# BYOB-BoosterPack-Template.net
KiCad netlist of a schematic drawn in EAGLE
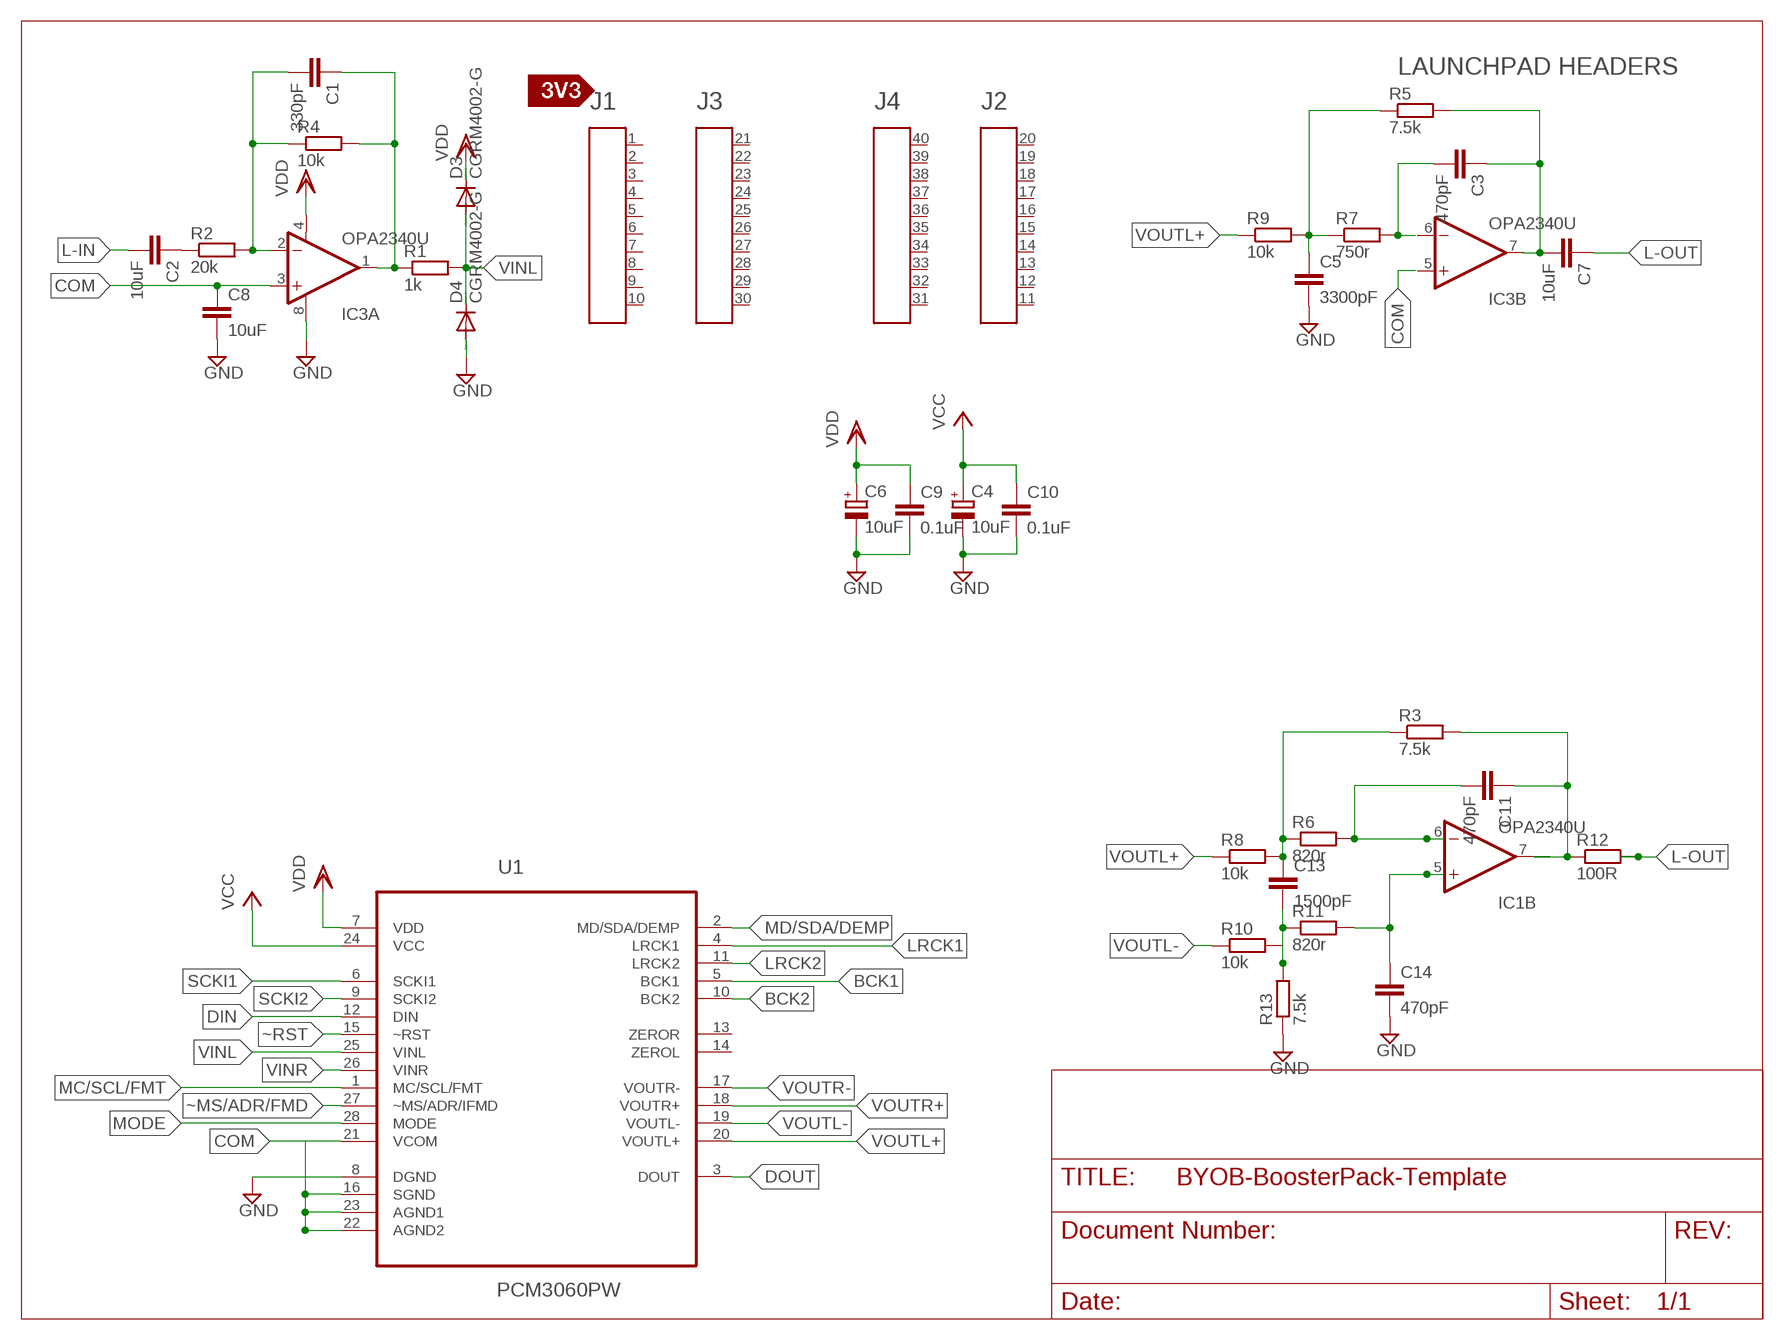
[diagram p0: schematic, sheet 1]

(export (version "E")
  (design (tool "Eeschema 10.0.6"))
  (components
    (comp (ref "A1")
      (value "HEADER4X10-BOOSTERPACK")
      (footprint "eagle-import:4X10-BOOSTERPACK")
      (libsource (lib "eagle-import") (part "HEADER4X10-BOOSTERPACK"))
    )
    (comp (ref "C1")
      (value "330pF")
      (footprint "eagle-import:C1608")
      (libsource (lib "eagle-import") (part "C-EUC1608"))
    )
    (comp (ref "C2")
      (value "10uF")
      (footprint "eagle-import:C1608")
      (libsource (lib "eagle-import") (part "C-EUC1608"))
    )
    (comp (ref "C3")
      (value "470pF")
      (footprint "eagle-import:C1608")
      (libsource (lib "eagle-import") (part "C-EUC1608"))
    )
    (comp (ref "C4")
      (value "10uF")
      (footprint "eagle-import:150CLZ-1010")
      (libsource (lib "eagle-import") (part "CPOL-EU150CLZ-1010"))
    )
    (comp (ref "C5")
      (value "3300pF")
      (footprint "eagle-import:C1608")
      (libsource (lib "eagle-import") (part "C-EUC1608"))
    )
    (comp (ref "C6")
      (value "10uF")
      (footprint "eagle-import:150CLZ-1010")
      (libsource (lib "eagle-import") (part "CPOL-EU150CLZ-1010"))
    )
    (comp (ref "C7")
      (value "10uF")
      (footprint "eagle-import:C1608")
      (libsource (lib "eagle-import") (part "C-EUC1608"))
    )
    (comp (ref "C8")
      (value "10uF")
      (footprint "eagle-import:C1608")
      (libsource (lib "eagle-import") (part "C-EUC1608"))
    )
    (comp (ref "C9")
      (value "0.1uF")
      (footprint "eagle-import:C1608")
      (libsource (lib "eagle-import") (part "C-EUC1608"))
    )
    (comp (ref "C10")
      (value "0.1uF")
      (footprint "eagle-import:C1608")
      (libsource (lib "eagle-import") (part "C-EUC1608"))
    )
    (comp (ref "C11")
      (value "470pF")
      (footprint "eagle-import:C1608")
      (libsource (lib "eagle-import") (part "C-EUC1608"))
    )
    (comp (ref "C13")
      (value "1500pF")
      (footprint "eagle-import:C1608")
      (libsource (lib "eagle-import") (part "C-EUC1608"))
    )
    (comp (ref "C14")
      (value "470pF")
      (footprint "eagle-import:C1608")
      (libsource (lib "eagle-import") (part "C-EUC1608"))
    )
    (comp (ref "D3")
      (value "CGRM4002-G")
      (footprint "eagle-import:SOD-123_MINI-SMA")
      (libsource (lib "eagle-import") (part "CGRM400-G2"))
    )
    (comp (ref "D4")
      (value "CGRM4002-G")
      (footprint "eagle-import:SOD-123_MINI-SMA")
      (libsource (lib "eagle-import") (part "CGRM400-G2"))
    )
    (comp (ref "IC1")
      (value "OPA2340U")
      (footprint "eagle-import:SO08")
      (fields (field (name "MF") "TEXAS INSTRUMENTS") (field (name "MPN") "OPA2340UA"))
      (libsource (lib "eagle-import") (part "OPA2340U"))
    )
    (comp (ref "IC3")
      (value "OPA2340U")
      (footprint "eagle-import:SO08")
      (fields (field (name "MF") "TEXAS INSTRUMENTS") (field (name "MPN") "OPA2340UA"))
      (libsource (lib "eagle-import") (part "OPA2340U"))
    )
    (comp (ref "R1")
      (value "1k")
      (footprint "eagle-import:R1206")
      (libsource (lib "eagle-import") (part "R-EU_R1206"))
    )
    (comp (ref "R2")
      (value "20k")
      (footprint "eagle-import:R1206")
      (libsource (lib "eagle-import") (part "R-EU_R1206"))
    )
    (comp (ref "R3")
      (value "7.5k")
      (footprint "eagle-import:R1206")
      (libsource (lib "eagle-import") (part "R-EU_R1206"))
    )
    (comp (ref "R4")
      (value "10k")
      (footprint "eagle-import:R1206")
      (libsource (lib "eagle-import") (part "R-EU_R1206"))
    )
    (comp (ref "R5")
      (value "7.5k")
      (footprint "eagle-import:R1206")
      (libsource (lib "eagle-import") (part "R-EU_R1206"))
    )
    (comp (ref "R6")
      (value "820r")
      (footprint "eagle-import:R1206")
      (libsource (lib "eagle-import") (part "R-EU_R1206"))
    )
    (comp (ref "R7")
      (value "750r")
      (footprint "eagle-import:R1206")
      (libsource (lib "eagle-import") (part "R-EU_R1206"))
    )
    (comp (ref "R8")
      (value "10k")
      (footprint "eagle-import:R1206")
      (libsource (lib "eagle-import") (part "R-EU_R1206"))
    )
    (comp (ref "R9")
      (value "10k")
      (footprint "eagle-import:R1206")
      (libsource (lib "eagle-import") (part "R-EU_R1206"))
    )
    (comp (ref "R10")
      (value "10k")
      (footprint "eagle-import:R1206")
      (libsource (lib "eagle-import") (part "R-EU_R1206"))
    )
    (comp (ref "R11")
      (value "820r")
      (footprint "eagle-import:R1206")
      (libsource (lib "eagle-import") (part "R-EU_R1206"))
    )
    (comp (ref "R12")
      (value "100R")
      (footprint "eagle-import:R1206")
      (libsource (lib "eagle-import") (part "R-EU_R1206"))
    )
    (comp (ref "R13")
      (value "7.5k")
      (footprint "eagle-import:R1206")
      (libsource (lib "eagle-import") (part "R-EU_R1206"))
    )
    (comp (ref "U$3")
      (value "SILK_3V3_TAG")
      (footprint "eagle-import:SILK_3V3_TAG")
      (libsource (lib "eagle-import") (part "SILK_3V3_TAG"))
    )
    (comp (ref "U1")
      (value "PCM3060PW")
      (footprint "eagle-import:SOP65P640X120-28N")
      (libsource (lib "eagle-import") (part "PCM3060PW"))
    )
  )
  (nets
    (net (code "1") (name "/~{MS{slash}ADR{slash}FMD}") (class "Default")
      (node (ref "U1") (pin "27") (pinfunction "~{MS/ADR/IFMD}_27") (pintype "input"))
    )
    (net (code "2") (name "/~{RST}") (class "Default")
      (node (ref "U1") (pin "15") (pinfunction "~{RST}_15") (pintype "input"))
    )
    (net (code "3") (name "BCK1") (class "Default")
      (node (ref "U1") (pin "5") (pinfunction "BCK1_5") (pintype "bidirectional"))
    )
    (net (code "4") (name "BCK2") (class "Default")
      (node (ref "U1") (pin "10") (pinfunction "BCK2_10") (pintype "bidirectional"))
    )
    (net (code "5") (name "COM") (class "Default")
      (node (ref "C14") (pin "1") (pinfunction "1_1") (pintype "passive"))
      (node (ref "C8") (pin "1") (pinfunction "1_1") (pintype "passive"))
      (node (ref "IC1") (pin "5") (pinfunction "+IN_5") (pintype "input"))
      (node (ref "IC3") (pin "3") (pinfunction "+IN_3") (pintype "input"))
      (node (ref "R11") (pin "2") (pinfunction "2_2") (pintype "passive"))
      (node (ref "U1") (pin "16") (pinfunction "SGND_16") (pintype "passive"))
      (node (ref "U1") (pin "21") (pinfunction "VCOM_21") (pintype "passive"))
      (node (ref "U1") (pin "22") (pinfunction "AGND2_22") (pintype "passive"))
      (node (ref "U1") (pin "23") (pinfunction "AGND1_23") (pintype "passive"))
    )
    (net (code "6") (name "DIN") (class "Default")
      (node (ref "U1") (pin "12") (pinfunction "DIN_12") (pintype "input"))
    )
    (net (code "7") (name "DOUT") (class "Default")
      (node (ref "U1") (pin "3") (pinfunction "DOUT_3") (pintype "output"))
    )
    (net (code "8") (name "GND") (class "Default")
      (node (ref "C10") (pin "2") (pinfunction "2_2") (pintype "passive"))
      (node (ref "C14") (pin "2") (pinfunction "2_2") (pintype "passive"))
      (node (ref "C4") (pin "-") (pinfunction "-_-") (pintype "passive"))
      (node (ref "C5") (pin "2") (pinfunction "2_2") (pintype "passive"))
      (node (ref "C6") (pin "-") (pinfunction "-_-") (pintype "passive"))
      (node (ref "C8") (pin "2") (pinfunction "2_2") (pintype "passive"))
      (node (ref "C9") (pin "2") (pinfunction "2_2") (pintype "passive"))
      (node (ref "D4") (pin "A") (pinfunction "A_A") (pintype "passive"))
      (node (ref "IC3") (pin "8") (pinfunction "V+_8") (pintype "power_in"))
      (node (ref "R13") (pin "1") (pinfunction "1_1") (pintype "passive"))
      (node (ref "U1") (pin "8") (pinfunction "DGND_8") (pintype "passive"))
    )
    (net (code "9") (name "L-IN") (class "Default")
      (node (ref "C2") (pin "2") (pinfunction "2_2") (pintype "passive"))
    )
    (net (code "10") (name "L-OUT") (class "Default")
      (node (ref "C7") (pin "1") (pinfunction "1_1") (pintype "passive"))
      (node (ref "R12") (pin "2") (pinfunction "2_2") (pintype "passive"))
    )
    (net (code "11") (name "LRCK1") (class "Default")
      (node (ref "U1") (pin "4") (pinfunction "LRCK1_4") (pintype "bidirectional"))
    )
    (net (code "12") (name "LRCK2") (class "Default")
      (node (ref "U1") (pin "11") (pinfunction "LRCK2_11") (pintype "bidirectional"))
    )
    (net (code "13") (name "MC{slash}SCL{slash}FMT") (class "Default")
      (node (ref "U1") (pin "1") (pinfunction "MC/SCL/FMT_1") (pintype "input"))
    )
    (net (code "14") (name "MD{slash}SDA{slash}DEMP") (class "Default")
      (node (ref "U1") (pin "2") (pinfunction "MD/SDA/DEMP_2") (pintype "bidirectional"))
    )
    (net (code "15") (name "MODE") (class "Default")
      (node (ref "U1") (pin "28") (pinfunction "MODE_28") (pintype "input"))
    )
    (net (code "16") (name "Net-(C2-Pad1)") (class "Default")
      (node (ref "C2") (pin "1") (pinfunction "1_1") (pintype "passive"))
      (node (ref "R2") (pin "1") (pinfunction "1_1") (pintype "passive"))
    )
    (net (code "17") (name "Net-(C3-Pad2)") (class "Default")
      (node (ref "C3") (pin "2") (pinfunction "2_2") (pintype "passive"))
      (node (ref "R7") (pin "2") (pinfunction "2_2") (pintype "passive"))
    )
    (net (code "18") (name "Net-(C5-Pad1)") (class "Default")
      (node (ref "C5") (pin "1") (pinfunction "1_1") (pintype "passive"))
      (node (ref "R5") (pin "1") (pinfunction "1_1") (pintype "passive"))
      (node (ref "R7") (pin "1") (pinfunction "1_1") (pintype "passive"))
      (node (ref "R9") (pin "2") (pinfunction "2_2") (pintype "passive"))
    )
    (net (code "19") (name "Net-(C13-Pad1)") (class "Default")
      (node (ref "C13") (pin "1") (pinfunction "1_1") (pintype "passive"))
      (node (ref "R3") (pin "1") (pinfunction "1_1") (pintype "passive"))
      (node (ref "R6") (pin "1") (pinfunction "1_1") (pintype "passive"))
      (node (ref "R8") (pin "2") (pinfunction "2_2") (pintype "passive"))
    )
    (net (code "20") (name "Net-(C13-Pad2)") (class "Default")
      (node (ref "C13") (pin "2") (pinfunction "2_2") (pintype "passive"))
      (node (ref "R10") (pin "2") (pinfunction "2_2") (pintype "passive"))
      (node (ref "R11") (pin "1") (pinfunction "1_1") (pintype "passive"))
      (node (ref "R13") (pin "2") (pinfunction "2_2") (pintype "passive"))
    )
    (net (code "21") (name "Net-(IC1B--IN)") (class "Default")
      (node (ref "C11") (pin "2") (pinfunction "2_2") (pintype "passive"))
      (node (ref "IC1") (pin "6") (pinfunction "-IN_6") (pintype "input"))
      (node (ref "R6") (pin "2") (pinfunction "2_2") (pintype "passive"))
    )
    (net (code "22") (name "Net-(IC1B-OUT)") (class "Default")
      (node (ref "C11") (pin "1") (pinfunction "1_1") (pintype "passive"))
      (node (ref "IC1") (pin "7") (pinfunction "OUT_7") (pintype "output"))
      (node (ref "R12") (pin "1") (pinfunction "1_1") (pintype "passive"))
      (node (ref "R3") (pin "2") (pinfunction "2_2") (pintype "passive"))
    )
    (net (code "23") (name "Net-(IC3A--IN)") (class "Default")
      (node (ref "C1") (pin "2") (pinfunction "2_2") (pintype "passive"))
      (node (ref "IC3") (pin "2") (pinfunction "-IN_2") (pintype "input"))
      (node (ref "R2") (pin "2") (pinfunction "2_2") (pintype "passive"))
      (node (ref "R4") (pin "1") (pinfunction "1_1") (pintype "passive"))
    )
    (net (code "24") (name "Net-(IC3A-OUT)") (class "Default")
      (node (ref "C1") (pin "1") (pinfunction "1_1") (pintype "passive"))
      (node (ref "IC3") (pin "1") (pinfunction "OUT_1") (pintype "output"))
      (node (ref "R1") (pin "1") (pinfunction "1_1") (pintype "passive"))
      (node (ref "R4") (pin "2") (pinfunction "2_2") (pintype "passive"))
    )
    (net (code "25") (name "Net-(IC3B-OUT)") (class "Default")
      (node (ref "C3") (pin "1") (pinfunction "1_1") (pintype "passive"))
      (node (ref "C7") (pin "2") (pinfunction "2_2") (pintype "passive"))
      (node (ref "IC3") (pin "7") (pinfunction "OUT_7") (pintype "output"))
      (node (ref "R5") (pin "2") (pinfunction "2_2") (pintype "passive"))
    )
    (net (code "26") (name "SCKI1") (class "Default")
      (node (ref "U1") (pin "6") (pinfunction "SCKI1_6") (pintype "input"))
    )
    (net (code "27") (name "SCKI2") (class "Default")
      (node (ref "U1") (pin "9") (pinfunction "SCKI2_9") (pintype "input"))
    )
    (net (code "28") (name "VCC") (class "Default")
      (node (ref "C10") (pin "1") (pinfunction "1_1") (pintype "passive"))
      (node (ref "C4") (pin "+") (pinfunction "+_+") (pintype "passive"))
      (node (ref "U1") (pin "24") (pinfunction "VCC_24") (pintype "power_in"))
    )
    (net (code "29") (name "VDD") (class "Default")
      (node (ref "C6") (pin "+") (pinfunction "+_+") (pintype "passive"))
      (node (ref "C9") (pin "1") (pinfunction "1_1") (pintype "passive"))
      (node (ref "D3") (pin "C") (pinfunction "C_C") (pintype "passive"))
      (node (ref "IC3") (pin "4") (pinfunction "V-_4") (pintype "power_in"))
      (node (ref "U1") (pin "7") (pinfunction "VDD_7") (pintype "power_in"))
    )
    (net (code "30") (name "VINL") (class "Default")
      (node (ref "D3") (pin "A") (pinfunction "A_A") (pintype "passive"))
      (node (ref "D4") (pin "C") (pinfunction "C_C") (pintype "passive"))
      (node (ref "R1") (pin "2") (pinfunction "2_2") (pintype "passive"))
      (node (ref "U1") (pin "25") (pinfunction "VINL_25") (pintype "input"))
    )
    (net (code "31") (name "VINR") (class "Default")
      (node (ref "U1") (pin "26") (pinfunction "VINR_26") (pintype "input"))
    )
    (net (code "32") (name "VOUTL+") (class "Default")
      (node (ref "R8") (pin "1") (pinfunction "1_1") (pintype "passive"))
      (node (ref "R9") (pin "1") (pinfunction "1_1") (pintype "passive"))
      (node (ref "U1") (pin "20") (pinfunction "VOUTL+_20") (pintype "output"))
    )
    (net (code "33") (name "VOUTL-") (class "Default")
      (node (ref "R10") (pin "1") (pinfunction "1_1") (pintype "passive"))
      (node (ref "U1") (pin "19") (pinfunction "VOUTL-_19") (pintype "output"))
    )
    (net (code "34") (name "VOUTR+") (class "Default")
      (node (ref "U1") (pin "18") (pinfunction "VOUTR+_18") (pintype "output"))
    )
    (net (code "35") (name "VOUTR-") (class "Default")
      (node (ref "U1") (pin "17") (pinfunction "VOUTR-_17") (pintype "output"))
    )
    (net (code "36") (name "unconnected-(A1-P$1-Pad1)") (class "Default")
      (node (ref "A1") (pin "1") (pinfunction "P$1_1") (pintype "bidirectional"))
    )
    (net (code "37") (name "unconnected-(A1-P$2-Pad2)") (class "Default")
      (node (ref "A1") (pin "2") (pinfunction "P$2_2") (pintype "bidirectional"))
    )
    (net (code "38") (name "unconnected-(A1-P$3-Pad3)") (class "Default")
      (node (ref "A1") (pin "3") (pinfunction "P$3_3") (pintype "bidirectional"))
    )
    (net (code "39") (name "unconnected-(A1-P$4-Pad4)") (class "Default")
      (node (ref "A1") (pin "4") (pinfunction "P$4_4") (pintype "bidirectional"))
    )
    (net (code "40") (name "unconnected-(A1-P$5-Pad5)") (class "Default")
      (node (ref "A1") (pin "5") (pinfunction "P$5_5") (pintype "bidirectional"))
    )
    (net (code "41") (name "unconnected-(A1-P$6-Pad6)") (class "Default")
      (node (ref "A1") (pin "6") (pinfunction "P$6_6") (pintype "bidirectional"))
    )
    (net (code "42") (name "unconnected-(A1-P$7-Pad7)") (class "Default")
      (node (ref "A1") (pin "7") (pinfunction "P$7_7") (pintype "bidirectional"))
    )
    (net (code "43") (name "unconnected-(A1-P$8-Pad8)") (class "Default")
      (node (ref "A1") (pin "8") (pinfunction "P$8_8") (pintype "bidirectional"))
    )
    (net (code "44") (name "unconnected-(A1-P$9-Pad9)") (class "Default")
      (node (ref "A1") (pin "9") (pinfunction "P$9_9") (pintype "bidirectional"))
    )
    (net (code "45") (name "unconnected-(A1-P$10-Pad10)") (class "Default")
      (node (ref "A1") (pin "10") (pinfunction "P$10_10") (pintype "bidirectional"))
    )
    (net (code "46") (name "unconnected-(A1-P$11-Pad11)") (class "Default")
      (node (ref "A1") (pin "11") (pinfunction "P$11_11") (pintype "bidirectional"))
    )
    (net (code "47") (name "unconnected-(A1-P$12-Pad12)") (class "Default")
      (node (ref "A1") (pin "12") (pinfunction "P$12_12") (pintype "bidirectional"))
    )
    (net (code "48") (name "unconnected-(A1-P$13-Pad13)") (class "Default")
      (node (ref "A1") (pin "13") (pinfunction "P$13_13") (pintype "bidirectional"))
    )
    (net (code "49") (name "unconnected-(A1-P$14-Pad14)") (class "Default")
      (node (ref "A1") (pin "14") (pinfunction "P$14_14") (pintype "bidirectional"))
    )
    (net (code "50") (name "unconnected-(A1-P$15-Pad15)") (class "Default")
      (node (ref "A1") (pin "15") (pinfunction "P$15_15") (pintype "bidirectional"))
    )
    (net (code "51") (name "unconnected-(A1-P$16-Pad16)") (class "Default")
      (node (ref "A1") (pin "16") (pinfunction "P$16_16") (pintype "bidirectional"))
    )
    (net (code "52") (name "unconnected-(A1-P$17-Pad17)") (class "Default")
      (node (ref "A1") (pin "17") (pinfunction "P$17_17") (pintype "bidirectional"))
    )
    (net (code "53") (name "unconnected-(A1-P$18-Pad18)") (class "Default")
      (node (ref "A1") (pin "18") (pinfunction "P$18_18") (pintype "bidirectional"))
    )
    (net (code "54") (name "unconnected-(A1-P$19-Pad19)") (class "Default")
      (node (ref "A1") (pin "19") (pinfunction "P$19_19") (pintype "bidirectional"))
    )
    (net (code "55") (name "unconnected-(A1-P$20-Pad20)") (class "Default")
      (node (ref "A1") (pin "20") (pinfunction "P$20_20") (pintype "bidirectional"))
    )
    (net (code "56") (name "unconnected-(A1-P$21-Pad21)") (class "Default")
      (node (ref "A1") (pin "21") (pinfunction "P$21_21") (pintype "bidirectional"))
    )
    (net (code "57") (name "unconnected-(A1-P$22-Pad22)") (class "Default")
      (node (ref "A1") (pin "22") (pinfunction "P$22_22") (pintype "bidirectional"))
    )
    (net (code "58") (name "unconnected-(A1-P$23-Pad23)") (class "Default")
      (node (ref "A1") (pin "23") (pinfunction "P$23_23") (pintype "bidirectional"))
    )
    (net (code "59") (name "unconnected-(A1-P$24-Pad24)") (class "Default")
      (node (ref "A1") (pin "24") (pinfunction "P$24_24") (pintype "bidirectional"))
    )
    (net (code "60") (name "unconnected-(A1-P$25-Pad25)") (class "Default")
      (node (ref "A1") (pin "25") (pinfunction "P$25_25") (pintype "bidirectional"))
    )
    (net (code "61") (name "unconnected-(A1-P$26-Pad26)") (class "Default")
      (node (ref "A1") (pin "26") (pinfunction "P$26_26") (pintype "bidirectional"))
    )
    (net (code "62") (name "unconnected-(A1-P$27-Pad27)") (class "Default")
      (node (ref "A1") (pin "27") (pinfunction "P$27_27") (pintype "bidirectional"))
    )
    (net (code "63") (name "unconnected-(A1-P$28-Pad28)") (class "Default")
      (node (ref "A1") (pin "28") (pinfunction "P$28_28") (pintype "bidirectional"))
    )
    (net (code "64") (name "unconnected-(A1-P$29-Pad29)") (class "Default")
      (node (ref "A1") (pin "29") (pinfunction "P$29_29") (pintype "bidirectional"))
    )
    (net (code "65") (name "unconnected-(A1-P$30-Pad30)") (class "Default")
      (node (ref "A1") (pin "30") (pinfunction "P$30_30") (pintype "bidirectional"))
    )
    (net (code "66") (name "unconnected-(A1-P$31-Pad31)") (class "Default")
      (node (ref "A1") (pin "31") (pinfunction "P$31_31") (pintype "bidirectional"))
    )
    (net (code "67") (name "unconnected-(A1-P$32-Pad32)") (class "Default")
      (node (ref "A1") (pin "32") (pinfunction "P$32_32") (pintype "bidirectional"))
    )
    (net (code "68") (name "unconnected-(A1-P$33-Pad33)") (class "Default")
      (node (ref "A1") (pin "33") (pinfunction "P$33_33") (pintype "bidirectional"))
    )
    (net (code "69") (name "unconnected-(A1-P$34-Pad34)") (class "Default")
      (node (ref "A1") (pin "34") (pinfunction "P$34_34") (pintype "bidirectional"))
    )
    (net (code "70") (name "unconnected-(A1-P$35-Pad35)") (class "Default")
      (node (ref "A1") (pin "35") (pinfunction "P$35_35") (pintype "bidirectional"))
    )
    (net (code "71") (name "unconnected-(A1-P$36-Pad36)") (class "Default")
      (node (ref "A1") (pin "36") (pinfunction "P$36_36") (pintype "bidirectional"))
    )
    (net (code "72") (name "unconnected-(A1-P$37-Pad37)") (class "Default")
      (node (ref "A1") (pin "37") (pinfunction "P$37_37") (pintype "bidirectional"))
    )
    (net (code "73") (name "unconnected-(A1-P$38-Pad38)") (class "Default")
      (node (ref "A1") (pin "38") (pinfunction "P$38_38") (pintype "bidirectional"))
    )
    (net (code "74") (name "unconnected-(A1-P$39-Pad39)") (class "Default")
      (node (ref "A1") (pin "39") (pinfunction "P$39_39") (pintype "bidirectional"))
    )
    (net (code "75") (name "unconnected-(A1-P$40-Pad40)") (class "Default")
      (node (ref "A1") (pin "40") (pinfunction "P$40_40") (pintype "bidirectional"))
    )
    (net (code "76") (name "unconnected-(IC3B-+IN-Pad5)") (class "Default")
      (node (ref "IC3") (pin "5") (pinfunction "+IN_5") (pintype "input"))
    )
    (net (code "77") (name "unconnected-(IC3B--IN-Pad6)") (class "Default")
      (node (ref "IC3") (pin "6") (pinfunction "-IN_6") (pintype "input"))
    )
    (net (code "78") (name "unconnected-(U1-ZEROL-Pad14)") (class "Default")
      (node (ref "U1") (pin "14") (pinfunction "ZEROL_14") (pintype "output"))
    )
    (net (code "79") (name "unconnected-(U1-ZEROR-Pad13)") (class "Default")
      (node (ref "U1") (pin "13") (pinfunction "ZEROR_13") (pintype "output"))
    )
  )
)
